# supply.net
KiCad netlist of a schematic drawn in Altium Designer
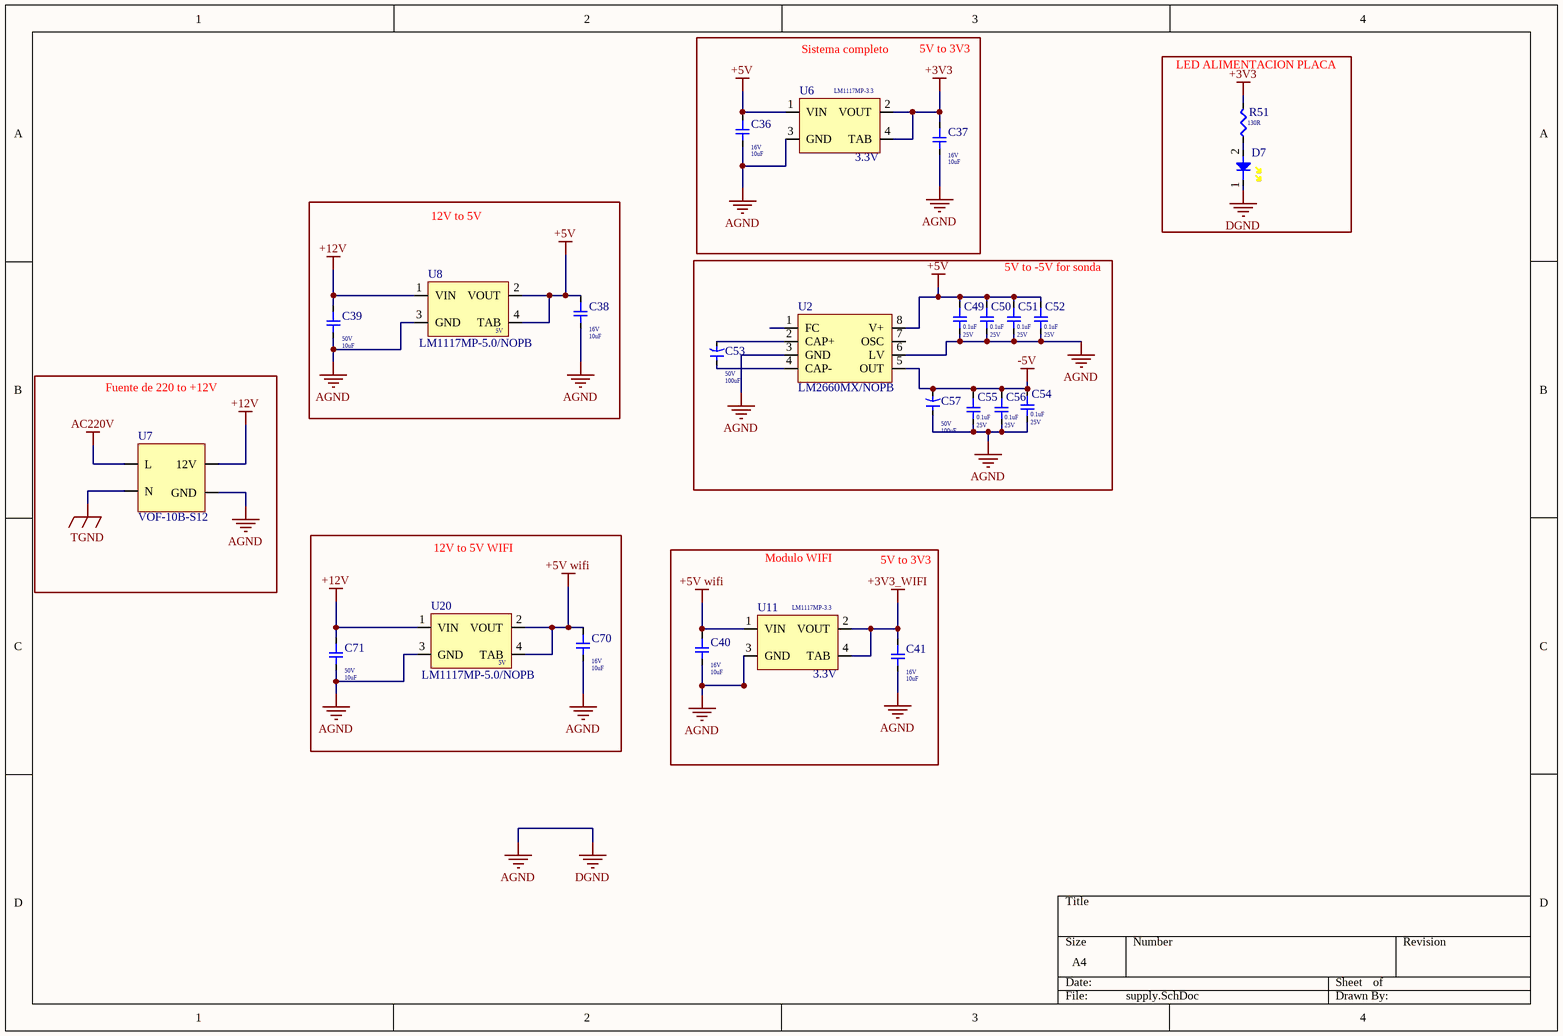
[diagram p0: supply.SchDoc]

(export (version "E")
  (design (tool "Eeschema 10.0.6"))
  (components
    (comp (ref "C36")
      (value "CAP_CL21A106KOCL3RC")
      (footprint "CAP smd 0805 OK")
      (description "CAP CER 10UF 16V X5R 0805")
      (fields
        (field (name "TOLERANCE") "10%")
        (field (name "VOLTAGE RATING") "16V")
        (field (name "CAPACITANCE") "10uF")
      )
      (libsource (lib "Cap") (part "CAP_CL21A106KOCL3RC"))
    )
    (comp (ref "C37")
      (value "CAP_CL21A106KOCL3RC")
      (footprint "CAP smd 0805 OK")
      (description "CAP CER 10UF 16V X5R 0805")
      (fields
        (field (name "TOLERANCE") "10%")
        (field (name "VOLTAGE RATING") "16V")
        (field (name "CAPACITANCE") "10uF")
      )
      (libsource (lib "Cap") (part "CAP_CL21A106KOCL3RC"))
    )
    (comp (ref "C38")
      (value "CAP_CL21A106KOCL3RC")
      (footprint "CAP smd 0805 OK")
      (description "CAP CER 10UF 16V X5R 0805")
      (fields
        (field (name "TOLERANCE") "10%")
        (field (name "VOLTAGE RATING") "16V")
        (field (name "CAPACITANCE") "10uF")
      )
      (libsource (lib "Cap") (part "CAP_CL21A106KOCL3RC"))
    )
    (comp (ref "C39")
      (value "CAP_CL31A106MBHNNNE")
      (footprint "cap smd 1206 ok")
      (description "Cap Ceramic 10uF 50V X5R 20% Pad SMD 1206 85°C T/R")
      (fields
        (field (name "TOLERANCE") "20%")
        (field (name "VOLTAGE RATING") "50V")
        (field (name "CAPACITANCE") "10uF")
      )
      (libsource (lib "Cap") (part "CAP_CL31A106MBHNNNE"))
    )
    (comp (ref "C40")
      (value "CAP_CL21A106KOCL3RC")
      (footprint "CAP smd 0805 OK")
      (description "CAP CER 10UF 16V X5R 0805")
      (fields
        (field (name "TOLERANCE") "10%")
        (field (name "VOLTAGE RATING") "16V")
        (field (name "CAPACITANCE") "10uF")
      )
      (libsource (lib "Cap") (part "CAP_CL21A106KOCL3RC"))
    )
    (comp (ref "C41")
      (value "CAP_CL21A106KOCL3RC")
      (footprint "CAP smd 0805 OK")
      (description "CAP CER 10UF 16V X5R 0805")
      (fields
        (field (name "TOLERANCE") "10%")
        (field (name "VOLTAGE RATING") "16V")
        (field (name "CAPACITANCE") "10uF")
      )
      (libsource (lib "Cap") (part "CAP_CL21A106KOCL3RC"))
    )
    (comp (ref "C49")
      (value "CAP_CC0805KRX7R8BB104_YAGEO")
      (footprint "CAP smd 0805 ok")
      (description "CAPACITOR, 0805, 100NF, 25V, REEL 4000")
      (fields
        (field (name "TOLERANCE") "10%")
        (field (name "VOLTAGE RATING") "25V")
        (field (name "CAPACITANCE") "0.1uF")
      )
      (libsource (lib "Cap") (part "CAP_CC0805KRX7R8BB104_YAGEO"))
    )
    (comp (ref "C50")
      (value "CAP_CC0805KRX7R8BB104_YAGEO")
      (footprint "CAP smd 0805 ok")
      (description "CAPACITOR, 0805, 100NF, 25V, REEL 4000")
      (fields
        (field (name "TOLERANCE") "10%")
        (field (name "VOLTAGE RATING") "25V")
        (field (name "CAPACITANCE") "0.1uF")
      )
      (libsource (lib "Cap") (part "CAP_CC0805KRX7R8BB104_YAGEO"))
    )
    (comp (ref "C51")
      (value "CAP_CC0805KRX7R8BB104_YAGEO")
      (footprint "CAP smd 0805 ok")
      (description "CAPACITOR, 0805, 100NF, 25V, REEL 4000")
      (fields
        (field (name "TOLERANCE") "10%")
        (field (name "VOLTAGE RATING") "25V")
        (field (name "CAPACITANCE") "0.1uF")
      )
      (libsource (lib "Cap") (part "CAP_CC0805KRX7R8BB104_YAGEO"))
    )
    (comp (ref "C52")
      (value "CAP_CC0805KRX7R8BB104_YAGEO")
      (footprint "CAP smd 0805 ok")
      (description "CAPACITOR, 0805, 100NF, 25V, REEL 4000")
      (fields
        (field (name "TOLERANCE") "10%")
        (field (name "VOLTAGE RATING") "25V")
        (field (name "CAPACITANCE") "0.1uF")
      )
      (libsource (lib "Cap") (part "CAP_CC0805KRX7R8BB104_YAGEO"))
    )
    (comp (ref "C53")
      (value "CAP_ESY107M050AG3AA_KEMET")
      (footprint "cap elec 8x11.5 ok")
      (fields
        (field (name "TOLERANCE") "20%")
        (field (name "VOLTAGE") "50V")
        (field (name "CAPACITANCE") "100uF")
      )
      (libsource (lib "Cap") (part "CAP_ESY107M050AG3AA_KEMET"))
    )
    (comp (ref "C54")
      (value "CAP_CC0805KRX7R8BB104_YAGEO")
      (footprint "CAP smd 0805 ok")
      (description "CAPACITOR, 0805, 100NF, 25V, REEL 4000")
      (fields
        (field (name "TOLERANCE") "10%")
        (field (name "VOLTAGE RATING") "25V")
        (field (name "CAPACITANCE") "0.1uF")
      )
      (libsource (lib "Cap") (part "CAP_CC0805KRX7R8BB104_YAGEO"))
    )
    (comp (ref "C55")
      (value "CAP_CC0805KRX7R8BB104_YAGEO")
      (footprint "CAP smd 0805 ok")
      (description "CAPACITOR, 0805, 100NF, 25V, REEL 4000")
      (fields
        (field (name "TOLERANCE") "10%")
        (field (name "VOLTAGE RATING") "25V")
        (field (name "CAPACITANCE") "0.1uF")
      )
      (libsource (lib "Cap") (part "CAP_CC0805KRX7R8BB104_YAGEO"))
    )
    (comp (ref "C56")
      (value "CAP_CC0805KRX7R8BB104_YAGEO")
      (footprint "CAP smd 0805 ok")
      (description "CAPACITOR, 0805, 100NF, 25V, REEL 4000")
      (fields
        (field (name "TOLERANCE") "10%")
        (field (name "VOLTAGE RATING") "25V")
        (field (name "CAPACITANCE") "0.1uF")
      )
      (libsource (lib "Cap") (part "CAP_CC0805KRX7R8BB104_YAGEO"))
    )
    (comp (ref "C57")
      (value "CAP_ESY107M050AG3AA_KEMET")
      (footprint "cap elec 8x11.5 ok")
      (fields
        (field (name "TOLERANCE") "20%")
        (field (name "VOLTAGE") "50V")
        (field (name "CAPACITANCE") "100uF")
      )
      (libsource (lib "Cap") (part "CAP_ESY107M050AG3AA_KEMET"))
    )
    (comp (ref "C70")
      (value "CAP_CL21A106KOCL3RC")
      (footprint "CAP smd 0805 OK")
      (description "CAP CER 10UF 16V X5R 0805")
      (fields
        (field (name "TOLERANCE") "10%")
        (field (name "VOLTAGE RATING") "16V")
        (field (name "CAPACITANCE") "10uF")
      )
      (libsource (lib "Cap") (part "CAP_CL21A106KOCL3RC"))
    )
    (comp (ref "C71")
      (value "CAP_CL31A106MBHNNNE")
      (footprint "cap smd 1206 ok")
      (description "Cap Ceramic 10uF 50V X5R 20% Pad SMD 1206 85°C T/R")
      (fields
        (field (name "TOLERANCE") "20%")
        (field (name "VOLTAGE RATING") "50V")
        (field (name "CAPACITANCE") "10uF")
      )
      (libsource (lib "Cap") (part "CAP_CL31A106MBHNNNE"))
    )
    (comp (ref "D7")
      (value "150080YS75000")
      (footprint "Diode smd 0805 yellow ok")
      (description "LED YELLOW CLEAR 0805 SMD")
      (libsource (lib "diode") (part "150080YS75000"))
    )
    (comp (ref "R51")
      (value "RC0805FR-07130RL")
      (footprint "res 0805 ok")
      (description "Res Thick Film smd 0805 130 Ohm 1% 0.125W(")
      (fields (field (name "TOLERANCE") "1%") (field (name "RESISTANCE") "130R"))
      (libsource (lib "res") (part "RC0805FR-07130RL"))
    )
    (comp (ref "U2")
      (value "LM2660MX/NOPB")
      (footprint "LM2660MX/NOPB ok")
      (description "Charge Pump INV/STPUP -1.5V to -5.5V 120mA 8-Pin SOIC T/R")
      (libsource (lib "ic") (part "LM2660MX/NOPB"))
    )
    (comp (ref "U6")
      (value "LM1117MP-3.3")
      (footprint "LM1117MP-3.3 ok")
      (description "LDO Regulator Pos 3.3V 0.8A 4-Pin(3+Tab) SOT-223 T/R")
      (fields (field (name "VOLTAGE") "3.3V") (field (name "MAX OUTPUT VOLTAGE") "3.3V"))
      (libsource (lib "ic") (part "LM1117MP-3.3"))
    )
    (comp (ref "U7")
      (value "VOF-10B-S12")
      (footprint "12v")
      (description "AC/DC CONVERTER 12V 10W")
      (libsource (lib "others") (part "VOF-10B-S12"))
    )
    (comp (ref "U8")
      (value "~")
      (footprint "LM1117MP-5.0/NOPB ok")
      (description "Space saving 800-mA low-dropout linear regulator with internal current limit 4-SOT-223 0 to 125")
      (fields
        (field (name "OUTPUT VOLTAGE") "5V")
        (field (name "MANUFACTURER PART NUMBER 1") "LM1117MP-5.0/NOPB")
      )
      (libsource (lib "ic") (part "LM1117MP-5.0/NOPB"))
    )
    (comp (ref "U11")
      (value "LM1117MP-3.3")
      (footprint "LM1117MP-3.3 ok")
      (description "LDO Regulator Pos 3.3V 0.8A 4-Pin(3+Tab) SOT-223 T/R")
      (fields (field (name "VOLTAGE") "3.3V") (field (name "MAX OUTPUT VOLTAGE") "3.3V"))
      (libsource (lib "ic") (part "LM1117MP-3.3"))
    )
    (comp (ref "U20")
      (value "~")
      (footprint "LM1117MP-5.0/NOPB ok")
      (description "Space saving 800-mA low-dropout linear regulator with internal current limit 4-SOT-223 0 to 125")
      (fields
        (field (name "OUTPUT VOLTAGE") "5V")
        (field (name "MANUFACTURER PART NUMBER 1") "LM1117MP-5.0/NOPB")
      )
      (libsource (lib "ic") (part "LM1117MP-5.0/NOPB"))
    )
  )
  (nets
    (net (code "1") (name "+3V3") (class "Default")
      (node (ref "C37") (pin "23") (pinfunction "23_23") (pintype "passive"))
      (node (ref "R51") (pin "2") (pinfunction "2_2") (pintype "passive"))
      (node (ref "U6") (pin "2") (pinfunction "VOUT_2") (pintype "passive"))
      (node (ref "U6") (pin "4") (pinfunction "TAB_4") (pintype "passive"))
    )
    (net (code "2") (name "+3V3_WIFI") (class "Default")
      (node (ref "C41") (pin "23") (pinfunction "23_23") (pintype "passive"))
      (node (ref "U11") (pin "2") (pinfunction "VOUT_2") (pintype "passive"))
      (node (ref "U11") (pin "4") (pinfunction "TAB_4") (pintype "passive"))
    )
    (net (code "3") (name "+5V") (class "Default")
      (node (ref "C36") (pin "23") (pinfunction "23_23") (pintype "passive"))
      (node (ref "C38") (pin "23") (pinfunction "23_23") (pintype "passive"))
      (node (ref "C49") (pin "23") (pinfunction "23_23") (pintype "passive"))
      (node (ref "C50") (pin "23") (pinfunction "23_23") (pintype "passive"))
      (node (ref "C51") (pin "23") (pinfunction "23_23") (pintype "passive"))
      (node (ref "C52") (pin "23") (pinfunction "23_23") (pintype "passive"))
      (node (ref "U2") (pin "8") (pinfunction "V+_8") (pintype "passive"))
      (node (ref "U6") (pin "1") (pinfunction "VIN_1") (pintype "passive"))
      (node (ref "U8") (pin "2") (pinfunction "VOUT_2") (pintype "passive"))
      (node (ref "U8") (pin "4") (pinfunction "TAB_4") (pintype "passive"))
    )
    (net (code "4") (name "+5V wifi") (class "Default")
      (node (ref "C40") (pin "23") (pinfunction "23_23") (pintype "passive"))
      (node (ref "C70") (pin "23") (pinfunction "23_23") (pintype "passive"))
      (node (ref "U11") (pin "1") (pinfunction "VIN_1") (pintype "passive"))
      (node (ref "U20") (pin "2") (pinfunction "VOUT_2") (pintype "passive"))
      (node (ref "U20") (pin "4") (pinfunction "TAB_4") (pintype "passive"))
    )
    (net (code "5") (name "+12V") (class "Default")
      (node (ref "C39") (pin "23") (pinfunction "23_23") (pintype "passive"))
      (node (ref "C71") (pin "23") (pinfunction "23_23") (pintype "passive"))
      (node (ref "U20") (pin "1") (pinfunction "VIN_1") (pintype "passive"))
      (node (ref "U7") (pin "3") (pinfunction "12V_3") (pintype "passive"))
      (node (ref "U8") (pin "1") (pinfunction "VIN_1") (pintype "passive"))
    )
    (net (code "6") (name "-5V") (class "Default")
      (node (ref "C54") (pin "23") (pinfunction "23_23") (pintype "passive"))
      (node (ref "C55") (pin "23") (pinfunction "23_23") (pintype "passive"))
      (node (ref "C56") (pin "23") (pinfunction "23_23") (pintype "passive"))
      (node (ref "C57") (pin "25") (pinfunction "25_25") (pintype "passive"))
      (node (ref "U2") (pin "5") (pinfunction "OUT_5") (pintype "passive"))
    )
    (net (code "7") (name "AC220V") (class "Default")
      (node (ref "U7") (pin "2") (pinfunction "L_2") (pintype "passive"))
    )
    (net (code "8") (name "AGND") (class "Default")
      (node (ref "C36") (pin "22") (pinfunction "22_22") (pintype "passive"))
      (node (ref "C37") (pin "22") (pinfunction "22_22") (pintype "passive"))
      (node (ref "C38") (pin "22") (pinfunction "22_22") (pintype "passive"))
      (node (ref "C39") (pin "22") (pinfunction "22_22") (pintype "passive"))
      (node (ref "C40") (pin "22") (pinfunction "22_22") (pintype "passive"))
      (node (ref "C41") (pin "22") (pinfunction "22_22") (pintype "passive"))
      (node (ref "C49") (pin "22") (pinfunction "22_22") (pintype "passive"))
      (node (ref "C50") (pin "22") (pinfunction "22_22") (pintype "passive"))
      (node (ref "C51") (pin "22") (pinfunction "22_22") (pintype "passive"))
      (node (ref "C52") (pin "22") (pinfunction "22_22") (pintype "passive"))
      (node (ref "C54") (pin "22") (pinfunction "22_22") (pintype "passive"))
      (node (ref "C55") (pin "22") (pinfunction "22_22") (pintype "passive"))
      (node (ref "C56") (pin "22") (pinfunction "22_22") (pintype "passive"))
      (node (ref "C57") (pin "24") (pinfunction "24_24") (pintype "passive"))
      (node (ref "C70") (pin "22") (pinfunction "22_22") (pintype "passive"))
      (node (ref "C71") (pin "22") (pinfunction "22_22") (pintype "passive"))
      (node (ref "D7") (pin "1") (pinfunction "1_1") (pintype "passive"))
      (node (ref "U11") (pin "3") (pinfunction "GND_3") (pintype "passive"))
      (node (ref "U2") (pin "3") (pinfunction "GND_3") (pintype "passive"))
      (node (ref "U2") (pin "6") (pinfunction "LV_6") (pintype "passive"))
      (node (ref "U20") (pin "3") (pinfunction "GND_3") (pintype "passive"))
      (node (ref "U6") (pin "3") (pinfunction "GND_3") (pintype "passive"))
      (node (ref "U7") (pin "4") (pinfunction "GND_4") (pintype "passive"))
      (node (ref "U8") (pin "3") (pinfunction "GND_3") (pintype "passive"))
    )
    (net (code "9") (name "Net-(D7-Pad2)") (class "Default")
      (node (ref "D7") (pin "2") (pinfunction "2_2") (pintype "passive"))
      (node (ref "R51") (pin "1") (pinfunction "1_1") (pintype "passive"))
    )
    (net (code "10") (name "Net-(U2-CAP+)") (class "Default")
      (node (ref "C53") (pin "25") (pinfunction "25_25") (pintype "passive"))
      (node (ref "U2") (pin "2") (pinfunction "CAP+_2") (pintype "passive"))
    )
    (net (code "11") (name "Net-(U2-CAP-)") (class "Default")
      (node (ref "C53") (pin "24") (pinfunction "24_24") (pintype "passive"))
      (node (ref "U2") (pin "4") (pinfunction "CAP-_4") (pintype "passive"))
    )
    (net (code "12") (name "TGND") (class "Default")
      (node (ref "U7") (pin "1") (pinfunction "N_1") (pintype "passive"))
    )
    (net (code "13") (name "unconnected-(U2-FC-Pad1)") (class "Default")
      (node (ref "U2") (pin "1") (pinfunction "FC_1") (pintype "passive"))
    )
    (net (code "14") (name "unconnected-(U2-OSC-Pad7)") (class "Default")
      (node (ref "U2") (pin "7") (pinfunction "OSC_7") (pintype "passive"))
    )
  )
)
